# SparkFun_Main_Board_Double_v22.net
KiCad netlist of a schematic drawn in EAGLE
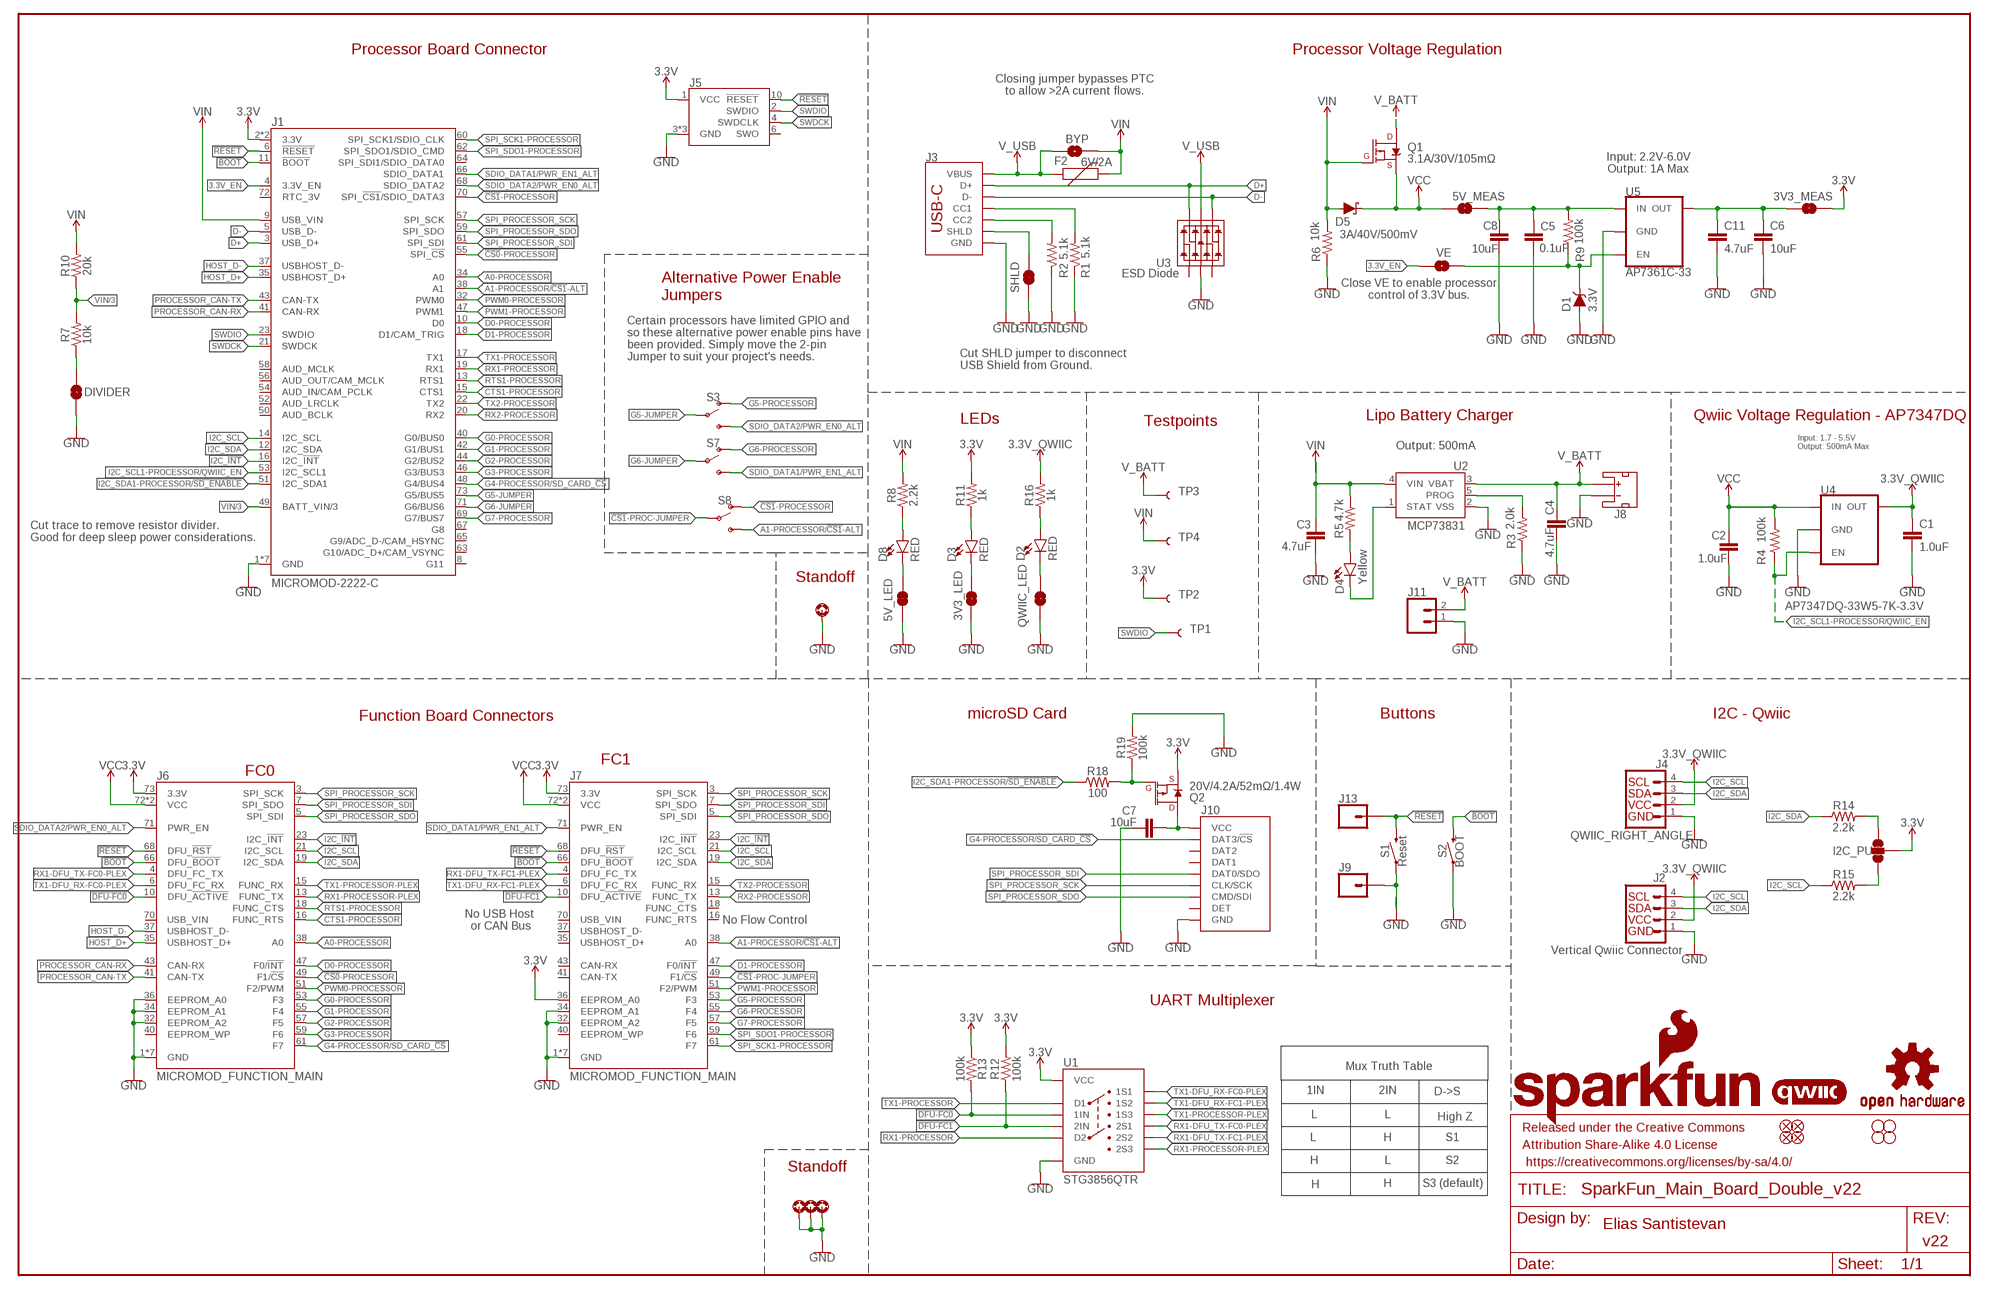
[diagram p0: schematic, sheet 1]

(export (version "E")
  (design (tool "Eeschema 10.0.6"))
  (components
    (comp (ref "3V3_LED")
      (value "JUMPER-SMT_2_NC_TRACE_SILK")
      (footprint "eagle-import:SMT-JUMPER_2_NC_TRACE_SILK")
      (libsource (lib "eagle-import") (part "JUMPER-SMT_2_NC_TRACE_SILK"))
    )
    (comp (ref "3V3_MEAS")
      (value "JUMPER-COMBO_2_NC_TRACE")
      (footprint "eagle-import:COMBO-JUMPER_2_NC_TRACE")
      (libsource (lib "eagle-import") (part "JUMPER-COMBO_2_NC_TRACE"))
    )
    (comp (ref "5V_LED")
      (value "JUMPER-SMT_2_NC_TRACE_SILK")
      (footprint "eagle-import:SMT-JUMPER_2_NC_TRACE_SILK")
      (libsource (lib "eagle-import") (part "JUMPER-SMT_2_NC_TRACE_SILK"))
    )
    (comp (ref "5V_MEAS")
      (value "JUMPER-COMBO_2_NC_TRACE")
      (footprint "eagle-import:COMBO-JUMPER_2_NC_TRACE")
      (libsource (lib "eagle-import") (part "JUMPER-COMBO_2_NC_TRACE"))
    )
    (comp (ref "BYP")
      (value "JUMPER-SMT_2_NO_SILK")
      (footprint "eagle-import:SMT-JUMPER_2_NO_SILK")
      (libsource (lib "eagle-import") (part "JUMPER-SMT_2_NO_SILK"))
    )
    (comp (ref "C1")
      (value "1.0uF")
      (footprint "eagle-import:0603")
      (libsource (lib "eagle-import") (part "1.0UF-0603-16V-10%"))
    )
    (comp (ref "C2")
      (value "1.0uF")
      (footprint "eagle-import:0603")
      (libsource (lib "eagle-import") (part "1.0UF-0603-16V-10%"))
    )
    (comp (ref "C3")
      (value "4.7uF")
      (footprint "eagle-import:0603")
      (libsource (lib "eagle-import") (part "4.7UF-0603-6.3V-(10%)"))
    )
    (comp (ref "C4")
      (value "4.7uF")
      (footprint "eagle-import:0603")
      (libsource (lib "eagle-import") (part "4.7UF-0603-35V-(20%)"))
    )
    (comp (ref "C5")
      (value "0.1uF")
      (footprint "eagle-import:0603")
      (libsource (lib "eagle-import") (part "0.1UF-0603-25V-(+80/-20%)"))
    )
    (comp (ref "C6")
      (value "10uF")
      (footprint "eagle-import:0805")
      (libsource (lib "eagle-import") (part "10UF-0805-10V-10%"))
    )
    (comp (ref "C7")
      (value "10uF")
      (footprint "eagle-import:0603")
      (libsource (lib "eagle-import") (part "10UF-0603-6.3V-20%"))
    )
    (comp (ref "C8")
      (value "10uF")
      (footprint "eagle-import:0805")
      (libsource (lib "eagle-import") (part "10UF-0805-10V-10%"))
    )
    (comp (ref "C11")
      (value "4.7uF")
      (footprint "eagle-import:0603")
      (libsource (lib "eagle-import") (part "4.7UF-0603-6.3V-(10%)"))
    )
    (comp (ref "D1")
      (value "3.3V")
      (footprint "eagle-import:SOD-323")
      (libsource (lib "eagle-import") (part "DIODE-ZENER-MM3Z3V3T1G"))
    )
    (comp (ref "D2")
      (value "RED")
      (footprint "eagle-import:LED-0603")
      (libsource (lib "eagle-import") (part "LED-RED0603"))
    )
    (comp (ref "D3")
      (value "RED")
      (footprint "eagle-import:LED-0603")
      (libsource (lib "eagle-import") (part "LED-RED0603"))
    )
    (comp (ref "D4")
      (value "Yellow")
      (footprint "eagle-import:LED-0603")
      (libsource (lib "eagle-import") (part "LED-YELLOW0603"))
    )
    (comp (ref "D5")
      (value "3A/40V/500mV")
      (footprint "eagle-import:SMA-DIODE")
      (libsource (lib "eagle-import") (part "DIODE-SCHOTTKY-B340A"))
    )
    (comp (ref "D8")
      (value "RED")
      (footprint "eagle-import:LED-0603")
      (libsource (lib "eagle-import") (part "LED-RED0603"))
    )
    (comp (ref "DIVIDER")
      (value "JUMPER-SMT_2_NC_TRACE_SILK")
      (footprint "eagle-import:SMT-JUMPER_2_NC_TRACE_SILK")
      (libsource (lib "eagle-import") (part "JUMPER-SMT_2_NC_TRACE_SILK"))
    )
    (comp (ref "F2")
      (value "6V/2A")
      (footprint "eagle-import:1210")
      (libsource (lib "eagle-import") (part "PPTC_6V2A"))
    )
    (comp (ref "FD1")
      (value "FIDUCIAL1X2")
      (footprint "eagle-import:FIDUCIAL-1X2")
      (libsource (lib "eagle-import") (part "FIDUCIAL1X2"))
    )
    (comp (ref "FD2")
      (value "FIDUCIAL1X2")
      (footprint "eagle-import:FIDUCIAL-1X2")
      (libsource (lib "eagle-import") (part "FIDUCIAL1X2"))
    )
    (comp (ref "FD3")
      (value "FIDUCIAL1X2")
      (footprint "eagle-import:FIDUCIAL-1X2")
      (libsource (lib "eagle-import") (part "FIDUCIAL1X2"))
    )
    (comp (ref "FD4")
      (value "FIDUCIAL1X2")
      (footprint "eagle-import:FIDUCIAL-1X2")
      (libsource (lib "eagle-import") (part "FIDUCIAL1X2"))
    )
    (comp (ref "FRAME1")
      (value "FRAME-LEDGER")
      (footprint "eagle-import:CREATIVE_COMMONS")
      (libsource (lib "eagle-import") (part "FRAME-LEDGER"))
    )
    (comp (ref "H2")
      (value "STAND-OFF-REFLOW-M2.5_2.5MM_TALL")
      (footprint "eagle-import:STAND-OFF-REFLOW-M2.5")
      (libsource (lib "eagle-import") (part "STAND-OFF-REFLOW-M2.5_2.5MM_TALL"))
    )
    (comp (ref "H3")
      (value "STAND-OFF-REFLOW-M2.5_2.5MM_TALL")
      (footprint "eagle-import:STAND-OFF-REFLOW-M2.5")
      (libsource (lib "eagle-import") (part "STAND-OFF-REFLOW-M2.5_2.5MM_TALL"))
    )
    (comp (ref "H4")
      (value "STAND-OFF-REFLOW-M2.5_2.5MM_TALL")
      (footprint "eagle-import:STAND-OFF-REFLOW-M2.5")
      (libsource (lib "eagle-import") (part "STAND-OFF-REFLOW-M2.5_2.5MM_TALL"))
    )
    (comp (ref "H8")
      (value "STAND-OFF-REFLOW-M2.5_2.5MM_TALL")
      (footprint "eagle-import:STAND-OFF-REFLOW-M2.5")
      (libsource (lib "eagle-import") (part "STAND-OFF-REFLOW-M2.5_2.5MM_TALL"))
    )
    (comp (ref "H14")
      (value "STAND-OFFTIGHT")
      (footprint "eagle-import:STAND-OFF-TIGHT")
      (libsource (lib "eagle-import") (part "STAND-OFFTIGHT"))
    )
    (comp (ref "H15")
      (value "STAND-OFFTIGHT")
      (footprint "eagle-import:STAND-OFF-TIGHT")
      (libsource (lib "eagle-import") (part "STAND-OFFTIGHT"))
    )
    (comp (ref "H16")
      (value "STAND-OFFTIGHT")
      (footprint "eagle-import:STAND-OFF-TIGHT")
      (libsource (lib "eagle-import") (part "STAND-OFFTIGHT"))
    )
    (comp (ref "H17")
      (value "STAND-OFFTIGHT")
      (footprint "eagle-import:STAND-OFF-TIGHT")
      (libsource (lib "eagle-import") (part "STAND-OFFTIGHT"))
    )
    (comp (ref "I2C_PU")
      (value "JUMPER-SMT_3_2-NC_TRACE_SILK")
      (footprint "eagle-import:SMT-JUMPER_3_2-NC_TRACE_SILK")
      (libsource (lib "eagle-import") (part "JUMPER-SMT_3_2-NC_TRACE_SILK"))
    )
    (comp (ref "J1")
      (value "MICROMOD-2222-C")
      (footprint "eagle-import:M.2-CONNECTOR-E")
      (libsource (lib "eagle-import") (part "MICROMOD-2222-C"))
    )
    (comp (ref "J2")
      (value "Vertical Qwiic Connector")
      (footprint "eagle-import:JST04_1MM_VERT")
      (libsource (lib "eagle-import") (part "QWIIC_CONNECTOR"))
    )
    (comp (ref "J3")
      (value "USB_C_2-LAYER_PADS")
      (footprint "eagle-import:USB-C-16P-2LAYER-PADS")
      (libsource (lib "eagle-import") (part "USB_C_2-LAYER_PADS"))
    )
    (comp (ref "J4")
      (value "QWIIC_RIGHT_ANGLE")
      (footprint "eagle-import:JST04_1MM_RA")
      (libsource (lib "eagle-import") (part "QWIIC_CONNECTORJS-1MM"))
    )
    (comp (ref "J5")
      (value "CORTEX_JTAG_DEBUG_MINIMUM_PTH")
      (footprint "eagle-import:2X5-PTH-1.27MM")
      (libsource (lib "eagle-import") (part "CORTEX_JTAG_DEBUG_MINIMUM_PTH"))
    )
    (comp (ref "J6")
      (value "MICROMOD_FUNCTION_MAIN")
      (footprint "eagle-import:M.2-CONNECTOR-E-FUNCTION-STANDARD")
      (libsource (lib "eagle-import") (part "MICROMOD_FUNCTION_MAIN"))
    )
    (comp (ref "J7")
      (value "MICROMOD_FUNCTION_MAIN")
      (footprint "eagle-import:M.2-CONNECTOR-E-FUNCTION-STANDARD")
      (libsource (lib "eagle-import") (part "MICROMOD_FUNCTION_MAIN"))
    )
    (comp (ref "J8")
      (value "JST_2MM_MALE")
      (footprint "eagle-import:JST-2-SMD")
      (libsource (lib "eagle-import") (part "JST_2MM_MALE"))
    )
    (comp (ref "J9")
      (value "CONN_01PTH_NO_SILK_YES_STOP")
      (footprint "eagle-import:1X01_NO_SILK")
      (libsource (lib "eagle-import") (part "CONN_01PTH_NO_SILK_YES_STOP"))
    )
    (comp (ref "J10")
      (value "MICRO-SD-PUSH-PUSH-EXT-PIN")
      (footprint "eagle-import:MICROSD-EXTERNALPIN")
      (libsource (lib "eagle-import") (part "MICRO-SD-PUSH-PUSH-EXT-PIN"))
    )
    (comp (ref "J11")
      (value "CONN_021X02_NO_SILK")
      (footprint "eagle-import:1X02_NO_SILK")
      (libsource (lib "eagle-import") (part "CONN_021X02_NO_SILK"))
    )
    (comp (ref "J13")
      (value "CONN_01PTH_NO_SILK_YES_STOP")
      (footprint "eagle-import:1X01_NO_SILK")
      (libsource (lib "eagle-import") (part "CONN_01PTH_NO_SILK_YES_STOP"))
    )
    (comp (ref "LOGO1")
      (value "QWIIC_LOGO_8MM")
      (footprint "eagle-import:QWIIC_8MM")
      (libsource (lib "eagle-import") (part "QWIIC_LOGO_8MM"))
    )
    (comp (ref "LOGO2")
      (value "SFE_LOGO_NAME_FLAME.3_INCH")
      (footprint "eagle-import:SFE_LOGO_NAME_FLAME_.3")
      (libsource (lib "eagle-import") (part "SFE_LOGO_NAME_FLAME.3_INCH"))
    )
    (comp (ref "LOGO3")
      (value "OSHW-LOGOL")
      (footprint "eagle-import:OSHW-LOGO-L")
      (libsource (lib "eagle-import") (part "OSHW-LOGOL"))
    )
    (comp (ref "Q1")
      (value "3.1A/30V/105mΩ")
      (footprint "eagle-import:SOT23-3")
      (libsource (lib "eagle-import") (part "MOSFET_PCH-DMG2307L"))
    )
    (comp (ref "Q2")
      (value "20V/4.2A/52mΩ/1.4W")
      (footprint "eagle-import:SOT23-3")
      (libsource (lib "eagle-import") (part "MOSFET_PCH-DMG2305UX-7"))
    )
    (comp (ref "QWIIC_LED")
      (value "JUMPER-SMT_2_NC_TRACE_SILK")
      (footprint "eagle-import:SMT-JUMPER_2_NC_TRACE_SILK")
      (libsource (lib "eagle-import") (part "JUMPER-SMT_2_NC_TRACE_SILK"))
    )
    (comp (ref "R1")
      (value "5.1k")
      (footprint "eagle-import:0603")
      (libsource (lib "eagle-import") (part "5.1KOHM5.1KOHM-0603-1/10W-1%"))
    )
    (comp (ref "R2")
      (value "5.1k")
      (footprint "eagle-import:0603")
      (libsource (lib "eagle-import") (part "5.1KOHM5.1KOHM-0603-1/10W-1%"))
    )
    (comp (ref "R3")
      (value "2.0k")
      (footprint "eagle-import:0603")
      (libsource (lib "eagle-import") (part "2.0KOHM-0603-1/10W-5%"))
    )
    (comp (ref "R4")
      (value "100k")
      (footprint "eagle-import:0603")
      (libsource (lib "eagle-import") (part "100KOHM-0603-1/10W-1%"))
    )
    (comp (ref "R5")
      (value "4.7k")
      (footprint "eagle-import:0603")
      (libsource (lib "eagle-import") (part "4.7KOHM-0603-1/10W-1%"))
    )
    (comp (ref "R6")
      (value "10k")
      (footprint "eagle-import:0603")
      (libsource (lib "eagle-import") (part "10KOHM-0603-1/10W-1%"))
    )
    (comp (ref "R7")
      (value "10k")
      (footprint "eagle-import:0603")
      (libsource (lib "eagle-import") (part "10KOHM-0603-1/10W-1%"))
    )
    (comp (ref "R8")
      (value "2.2k")
      (footprint "eagle-import:0603")
      (libsource (lib "eagle-import") (part "2.2KOHM-0603-1/10W-1%"))
    )
    (comp (ref "R9")
      (value "100k")
      (footprint "eagle-import:0603")
      (libsource (lib "eagle-import") (part "100KOHM-0603-1/10W-1%"))
    )
    (comp (ref "R10")
      (value "20k")
      (footprint "eagle-import:0603")
      (libsource (lib "eagle-import") (part "20KOHM-0603-1/10W-1%"))
    )
    (comp (ref "R11")
      (value "1k")
      (footprint "eagle-import:0603")
      (libsource (lib "eagle-import") (part "1KOHM-0603-1/10W-1%"))
    )
    (comp (ref "R12")
      (value "100k")
      (footprint "eagle-import:0603")
      (libsource (lib "eagle-import") (part "100KOHM-0603-1/10W-1%"))
    )
    (comp (ref "R13")
      (value "100k")
      (footprint "eagle-import:0603")
      (libsource (lib "eagle-import") (part "100KOHM-0603-1/10W-1%"))
    )
    (comp (ref "R14")
      (value "2.2k")
      (footprint "eagle-import:0603")
      (libsource (lib "eagle-import") (part "2.2KOHM-0603-1/10W-1%"))
    )
    (comp (ref "R15")
      (value "2.2k")
      (footprint "eagle-import:0603")
      (libsource (lib "eagle-import") (part "2.2KOHM-0603-1/10W-1%"))
    )
    (comp (ref "R16")
      (value "1k")
      (footprint "eagle-import:0603")
      (libsource (lib "eagle-import") (part "1KOHM-0603-1/10W-1%"))
    )
    (comp (ref "R18")
      (value "100")
      (footprint "eagle-import:0603")
      (libsource (lib "eagle-import") (part "100OHM-0603-1/10W-1%"))
    )
    (comp (ref "R19")
      (value "100k")
      (footprint "eagle-import:0603")
      (libsource (lib "eagle-import") (part "100KOHM-0603-1/10W-1%"))
    )
    (comp (ref "S1")
      (value "Reset")
      (footprint "eagle-import:TACTILE_SWITCH_SMD_5.2MM")
      (libsource (lib "eagle-import") (part "MOMENTARY-SWITCH-SPST-SMD-5.2-TALL-REDUNDANT"))
    )
    (comp (ref "S2")
      (value "BOOT")
      (footprint "eagle-import:TACTILE_SWITCH_SMD_5.2MM")
      (libsource (lib "eagle-import") (part "MOMENTARY-SWITCH-SPST-SMD-5.2-TALL-REDUNDANT"))
    )
    (comp (ref "S3")
      (value "SWITCH-SPDT-SMD-RIGHT-ANGLE")
      (footprint "eagle-import:SWITCH_SPST_SMD_A")
      (libsource (lib "eagle-import") (part "SWITCH-SPDT-SMD-RIGHT-ANGLE"))
    )
    (comp (ref "S7")
      (value "SWITCH-SPDT-SMD-RIGHT-ANGLE")
      (footprint "eagle-import:SWITCH_SPST_SMD_A")
      (libsource (lib "eagle-import") (part "SWITCH-SPDT-SMD-RIGHT-ANGLE"))
    )
    (comp (ref "S8")
      (value "SWITCH-SPDT-SMD-RIGHT-ANGLE")
      (footprint "eagle-import:SWITCH_SPST_SMD_A")
      (libsource (lib "eagle-import") (part "SWITCH-SPDT-SMD-RIGHT-ANGLE"))
    )
    (comp (ref "SHLD")
      (value "JUMPER-SMT_2_NC_TRACE_SILK")
      (footprint "eagle-import:SMT-JUMPER_2_NC_TRACE_SILK")
      (libsource (lib "eagle-import") (part "JUMPER-SMT_2_NC_TRACE_SILK"))
    )
    (comp (ref "TP1")
      (value "TEST-POINT3X5")
      (footprint "eagle-import:PAD.03X.05")
      (libsource (lib "eagle-import") (part "TEST-POINT3X5"))
    )
    (comp (ref "TP2")
      (value "TEST-POINT3X5")
      (footprint "eagle-import:PAD.03X.05")
      (libsource (lib "eagle-import") (part "TEST-POINT3X5"))
    )
    (comp (ref "TP3")
      (value "TEST-POINT3X5")
      (footprint "eagle-import:PAD.03X.05")
      (libsource (lib "eagle-import") (part "TEST-POINT3X5"))
    )
    (comp (ref "TP4")
      (value "TEST-POINT3X5")
      (footprint "eagle-import:PAD.03X.05")
      (libsource (lib "eagle-import") (part "TEST-POINT3X5"))
    )
    (comp (ref "U1")
      (value "STG3856QTR")
      (footprint "eagle-import:STG3856")
      (libsource (lib "eagle-import") (part "STG3856QTR"))
    )
    (comp (ref "U2")
      (value "MCP73831")
      (footprint "eagle-import:SOT23-5")
      (libsource (lib "eagle-import") (part "MCP73831"))
    )
    (comp (ref "U3")
      (value "ESD Diode")
      (footprint "eagle-import:SOT-23-6")
      (libsource (lib "eagle-import") (part "TVS_DIODE_ARRAYSMD"))
    )
    (comp (ref "U4")
      (value "AP7347DQ-33W5-7K-3.3V")
      (footprint "eagle-import:SOT25")
      (libsource (lib "eagle-import") (part "AP7347DQ-33W5-7K-3.3V"))
    )
    (comp (ref "U5")
      (value "AP7361C-33")
      (footprint "eagle-import:UDFN-8")
      (libsource (lib "eagle-import") (part "AP7361C-33FGEUDFN-8"))
    )
    (comp (ref "VE")
      (value "JUMPER-SMT_2_NO_SILK")
      (footprint "eagle-import:SMT-JUMPER_2_NO_SILK")
      (libsource (lib "eagle-import") (part "JUMPER-SMT_2_NO_SILK"))
    )
  )
  (nets
    (net (code "1") (name "/A1-PROCESSOR{slash}~{CS1}-ALT") (class "Default")
      (node (ref "J1") (pin "38") (pinfunction "A1_38") (pintype "bidirectional"))
      (node (ref "J7") (pin "38") (pinfunction "A0_38") (pintype "bidirectional"))
      (node (ref "S8") (pin "3") (pinfunction "S_3") (pintype "passive"))
    )
    (net (code "2") (name "/G4-PROCESSOR{slash}SD_CARD_~{CS}") (class "Default")
      (node (ref "J1") (pin "48") (pinfunction "G4/BUS4_48") (pintype "bidirectional"))
      (node (ref "J10") (pin "2") (pinfunction "DAT3/~{CS}_2") (pintype "bidirectional"))
      (node (ref "J6") (pin "61") (pinfunction "F7_61") (pintype "bidirectional"))
    )
    (net (code "3") (name "/I2C_SDA1-PROCESSOR{slash}~{SD_ENABLE}") (class "Default")
      (node (ref "J1") (pin "51") (pinfunction "I2C_SDA1_51") (pintype "bidirectional"))
      (node (ref "R18") (pin "1") (pinfunction "1_1") (pintype "passive"))
    )
    (net (code "4") (name "/I2C_~{INT}") (class "Default")
      (node (ref "J1") (pin "16") (pinfunction "I2C_~{INT}_16") (pintype "bidirectional"))
      (node (ref "J6") (pin "23") (pinfunction "I2C_~{INT}_23") (pintype "bidirectional"))
      (node (ref "J7") (pin "23") (pinfunction "I2C_~{INT}_23") (pintype "bidirectional"))
    )
    (net (code "5") (name "/~{BOOT}") (class "Default")
      (node (ref "J1") (pin "11") (pinfunction "~{BOOT}_11") (pintype "bidirectional"))
      (node (ref "J6") (pin "66") (pinfunction "DFU_~{BOOT}_66") (pintype "bidirectional"))
      (node (ref "J7") (pin "66") (pinfunction "DFU_~{BOOT}_66") (pintype "bidirectional"))
      (node (ref "S2") (pin "3") (pinfunction "2_3") (pintype "passive"))
      (node (ref "S2") (pin "4") (pinfunction "2_4") (pintype "passive"))
    )
    (net (code "6") (name "/~{CS0}-PROCESSOR") (class "Default")
      (node (ref "J1") (pin "55") (pinfunction "SPI_~{CS}_55") (pintype "bidirectional"))
      (node (ref "J6") (pin "49") (pinfunction "F1/~{CS}_49") (pintype "bidirectional"))
    )
    (net (code "7") (name "/~{CS1}-PROC-JUMPER") (class "Default")
      (node (ref "J7") (pin "49") (pinfunction "F1/~{CS}_49") (pintype "bidirectional"))
      (node (ref "S8") (pin "2") (pinfunction "P_2") (pintype "passive"))
    )
    (net (code "8") (name "/~{CS1}-PROCESSOR") (class "Default")
      (node (ref "J1") (pin "70") (pinfunction "SPI_~{CS1}/SDIO_DATA3_70") (pintype "bidirectional"))
      (node (ref "S8") (pin "1") (pinfunction "O_1") (pintype "passive"))
    )
    (net (code "9") (name "/~{DFU-FC0}") (class "Default")
      (node (ref "J6") (pin "10") (pinfunction "DFU_~{ACTIVE}_10") (pintype "bidirectional"))
      (node (ref "R13") (pin "2") (pinfunction "2_2") (pintype "passive"))
      (node (ref "U1") (pin "P12") (pinfunction "1IN_P12") (pintype "bidirectional"))
    )
    (net (code "10") (name "/~{DFU-FC1}") (class "Default")
      (node (ref "J7") (pin "10") (pinfunction "DFU_~{ACTIVE}_10") (pintype "bidirectional"))
      (node (ref "R12") (pin "1") (pinfunction "1_1") (pintype "passive"))
      (node (ref "U1") (pin "P10") (pinfunction "2IN_P10") (pintype "bidirectional"))
    )
    (net (code "11") (name "/~{RESET}") (class "Default")
      (node (ref "J1") (pin "6") (pinfunction "~{RESET}_6") (pintype "bidirectional"))
      (node (ref "J13") (pin "1") (pinfunction "1_1") (pintype "passive"))
      (node (ref "J5") (pin "10") (pinfunction "~{RESET}_10") (pintype "bidirectional"))
      (node (ref "J6") (pin "68") (pinfunction "DFU_~{RST}_68") (pintype "bidirectional"))
      (node (ref "J7") (pin "68") (pinfunction "DFU_~{RST}_68") (pintype "bidirectional"))
      (node (ref "S1") (pin "3") (pinfunction "2_3") (pintype "passive"))
      (node (ref "S1") (pin "4") (pinfunction "2_4") (pintype "passive"))
    )
    (net (code "12") (name "3.3V") (class "Default")
      (node (ref "3V3_MEAS") (pin "2") (pinfunction "2_2") (pintype "passive"))
      (node (ref "3V3_MEAS") (pin "4") (pinfunction "2_4") (pintype "passive"))
      (node (ref "I2C_PU") (pin "2") (pinfunction "2_2") (pintype "passive"))
      (node (ref "J1") (pin "2") (pinfunction "3.3V_2") (pintype "bidirectional"))
      (node (ref "J1") (pin "74") (pinfunction "3.3V_74") (pintype "bidirectional"))
      (node (ref "J5") (pin "1") (pinfunction "VCC_1") (pintype "bidirectional"))
      (node (ref "J6") (pin "73") (pinfunction "3.3V_73") (pintype "bidirectional"))
      (node (ref "J7") (pin "36") (pinfunction "EEPROM_A0_36") (pintype "bidirectional"))
      (node (ref "J7") (pin "73") (pinfunction "3.3V_73") (pintype "bidirectional"))
      (node (ref "Q2") (pin "2") (pinfunction "S_2") (pintype "bidirectional"))
      (node (ref "R11") (pin "2") (pinfunction "2_2") (pintype "passive"))
      (node (ref "R12") (pin "2") (pinfunction "2_2") (pintype "passive"))
      (node (ref "R13") (pin "1") (pinfunction "1_1") (pintype "passive"))
      (node (ref "TP2") (pin "1") (pinfunction "1_1") (pintype "bidirectional"))
      (node (ref "U1") (pin "P11") (pinfunction "VCC_P11") (pintype "power_in"))
    )
    (net (code "13") (name "3.3V_EN") (class "Default")
      (node (ref "J1") (pin "4") (pinfunction "3.3V_EN_4") (pintype "bidirectional"))
      (node (ref "VE") (pin "1") (pinfunction "1_1") (pintype "passive"))
    )
    (net (code "14") (name "3.3V_QWIIC") (class "Default")
      (node (ref "C1") (pin "1") (pinfunction "1_1") (pintype "passive"))
      (node (ref "J2") (pin "2") (pinfunction "2_2") (pintype "power_in"))
      (node (ref "J4") (pin "2") (pinfunction "2_2") (pintype "power_in"))
      (node (ref "R16") (pin "2") (pinfunction "2_2") (pintype "passive"))
      (node (ref "U4") (pin "5") (pinfunction "OUT_5") (pintype "passive"))
    )
    (net (code "15") (name "A0-PROCESSOR") (class "Default")
      (node (ref "J1") (pin "34") (pinfunction "A0_34") (pintype "bidirectional"))
      (node (ref "J6") (pin "38") (pinfunction "A0_38") (pintype "bidirectional"))
    )
    (net (code "16") (name "CTS1-PROCESSOR") (class "Default")
      (node (ref "J1") (pin "15") (pinfunction "CTS1_15") (pintype "bidirectional"))
      (node (ref "J6") (pin "16") (pinfunction "FUNC_RTS_16") (pintype "bidirectional"))
    )
    (net (code "17") (name "D+") (class "Default")
      (node (ref "J1") (pin "3") (pinfunction "USB_D+_3") (pintype "bidirectional"))
      (node (ref "J3") (pin "A6") (pinfunction "D+_A6") (pintype "bidirectional"))
      (node (ref "J3") (pin "B6") (pinfunction "D+_B6") (pintype "bidirectional"))
      (node (ref "U3") (pin "6") (pinfunction "IO4_6") (pintype "bidirectional"))
    )
    (net (code "18") (name "D-") (class "Default")
      (node (ref "J1") (pin "5") (pinfunction "USB_D-_5") (pintype "bidirectional"))
      (node (ref "J3") (pin "A7") (pinfunction "D-_A7") (pintype "bidirectional"))
      (node (ref "J3") (pin "B7") (pinfunction "D-_B7") (pintype "bidirectional"))
      (node (ref "U3") (pin "4") (pinfunction "IO3_4") (pintype "bidirectional"))
    )
    (net (code "19") (name "D0-PROCESSOR") (class "Default")
      (node (ref "J1") (pin "10") (pinfunction "D0_10") (pintype "bidirectional"))
      (node (ref "J6") (pin "47") (pinfunction "F0/~{INT}_47") (pintype "bidirectional"))
    )
    (net (code "20") (name "D1-PROCESSOR") (class "Default")
      (node (ref "J1") (pin "18") (pinfunction "D1/CAM_TRIG_18") (pintype "bidirectional"))
      (node (ref "J7") (pin "47") (pinfunction "F0/~{INT}_47") (pintype "bidirectional"))
    )
    (net (code "21") (name "G0-PROCESSOR") (class "Default")
      (node (ref "J1") (pin "40") (pinfunction "G0/BUS0_40") (pintype "bidirectional"))
      (node (ref "J6") (pin "53") (pinfunction "F3_53") (pintype "bidirectional"))
    )
    (net (code "22") (name "G1-PROCESSOR") (class "Default")
      (node (ref "J1") (pin "42") (pinfunction "G1/BUS1_42") (pintype "bidirectional"))
      (node (ref "J6") (pin "55") (pinfunction "F4_55") (pintype "bidirectional"))
    )
    (net (code "23") (name "G2-PROCESSOR") (class "Default")
      (node (ref "J1") (pin "44") (pinfunction "G2/BUS2_44") (pintype "bidirectional"))
      (node (ref "J6") (pin "57") (pinfunction "F5_57") (pintype "bidirectional"))
    )
    (net (code "24") (name "G3-PROCESSOR") (class "Default")
      (node (ref "J1") (pin "46") (pinfunction "G3/BUS3_46") (pintype "bidirectional"))
      (node (ref "J6") (pin "59") (pinfunction "F6_59") (pintype "bidirectional"))
    )
    (net (code "25") (name "G5-JUMPER") (class "Default")
      (node (ref "J1") (pin "73") (pinfunction "G5/BUS5_73") (pintype "bidirectional"))
      (node (ref "S3") (pin "2") (pinfunction "P_2") (pintype "passive"))
    )
    (net (code "26") (name "G5-PROCESSOR") (class "Default")
      (node (ref "J7") (pin "53") (pinfunction "F3_53") (pintype "bidirectional"))
      (node (ref "S3") (pin "1") (pinfunction "O_1") (pintype "passive"))
    )
    (net (code "27") (name "G6-JUMPER") (class "Default")
      (node (ref "J1") (pin "71") (pinfunction "G6/BUS6_71") (pintype "bidirectional"))
      (node (ref "S7") (pin "2") (pinfunction "P_2") (pintype "passive"))
    )
    (net (code "28") (name "G6-PROCESSOR") (class "Default")
      (node (ref "J7") (pin "55") (pinfunction "F4_55") (pintype "bidirectional"))
      (node (ref "S7") (pin "1") (pinfunction "O_1") (pintype "passive"))
    )
    (net (code "29") (name "G7-PROCESSOR") (class "Default")
      (node (ref "J1") (pin "69") (pinfunction "G7/BUS7_69") (pintype "bidirectional"))
      (node (ref "J7") (pin "57") (pinfunction "F5_57") (pintype "bidirectional"))
    )
    (net (code "30") (name "GND") (class "Default")
      (node (ref "3V3_LED") (pin "1") (pinfunction "1_1") (pintype "passive"))
      (node (ref "5V_LED") (pin "1") (pinfunction "1_1") (pintype "passive"))
      (node (ref "C1") (pin "2") (pinfunction "2_2") (pintype "passive"))
      (node (ref "C11") (pin "2") (pinfunction "2_2") (pintype "passive"))
      (node (ref "C2") (pin "2") (pinfunction "2_2") (pintype "passive"))
      (node (ref "C3") (pin "2") (pinfunction "2_2") (pintype "passive"))
      (node (ref "C4") (pin "2") (pinfunction "2_2") (pintype "passive"))
      (node (ref "C5") (pin "2") (pinfunction "2_2") (pintype "passive"))
      (node (ref "C6") (pin "2") (pinfunction "2_2") (pintype "passive"))
      (node (ref "C7") (pin "1") (pinfunction "1_1") (pintype "passive"))
      (node (ref "C8") (pin "2") (pinfunction "2_2") (pintype "passive"))
      (node (ref "D1") (pin "A") (pinfunction "A_A") (pintype "passive"))
      (node (ref "DIVIDER") (pin "1") (pinfunction "1_1") (pintype "passive"))
      (node (ref "H2") (pin "1") (pinfunction "1_1") (pintype "bidirectional"))
      (node (ref "H3") (pin "1") (pinfunction "1_1") (pintype "bidirectional"))
      (node (ref "H4") (pin "1") (pinfunction "1_1") (pintype "bidirectional"))
      (node (ref "H8") (pin "1") (pinfunction "1_1") (pintype "bidirectional"))
      (node (ref "J1") (pin "1") (pinfunction "GND_1") (pintype "bidirectional"))
      (node (ref "J1") (pin "33") (pinfunction "GND_33") (pintype "bidirectional"))
      (node (ref "J1") (pin "36") (pinfunction "GND_36") (pintype "bidirectional"))
      (node (ref "J1") (pin "39") (pinfunction "GND_39") (pintype "bidirectional"))
      (node (ref "J1") (pin "45") (pinfunction "GND_45") (pintype "bidirectional"))
      (node (ref "J1") (pin "7") (pinfunction "GND_7") (pintype "bidirectional"))
      (node (ref "J1") (pin "75") (pinfunction "GND_75") (pintype "bidirectional"))
      (node (ref "J10") (pin "10") (pinfunction "GND_10") (pintype "bidirectional"))
      (node (ref "J10") (pin "11") (pinfunction "GND_11") (pintype "bidirectional"))
      (node (ref "J10") (pin "12") (pinfunction "GND_12") (pintype "bidirectional"))
      (node (ref "J10") (pin "13") (pinfunction "GND_13") (pintype "bidirectional"))
      (node (ref "J10") (pin "6") (pinfunction "GND_6") (pintype "bidirectional"))
      (node (ref "J11") (pin "1") (pinfunction "1_1") (pintype "passive"))
      (node (ref "J2") (pin "1") (pinfunction "1_1") (pintype "power_in"))
      (node (ref "J3") (pin "GND") (pinfunction "GND_GND") (pintype "bidirectional"))
      (node (ref "J3") (pin "GND2") (pinfunction "GND_GND2") (pintype "bidirectional"))
      (node (ref "J4") (pin "1") (pinfunction "1_1") (pintype "power_in"))
      (node (ref "J5") (pin "3") (pinfunction "GND_3") (pintype "bidirectional"))
      (node (ref "J5") (pin "5") (pinfunction "GND_5") (pintype "bidirectional"))
      (node (ref "J5") (pin "9") (pinfunction "GND_9") (pintype "bidirectional"))
      (node (ref "J6") (pin "1") (pinfunction "GND_1") (pintype "bidirectional"))
      (node (ref "J6") (pin "2") (pinfunction "GND_2") (pintype "bidirectional"))
      (node (ref "J6") (pin "32") (pinfunction "EEPROM_A2_32") (pintype "bidirectional"))
      (node (ref "J6") (pin "33") (pinfunction "GND_33") (pintype "bidirectional"))
      (node (ref "J6") (pin "34") (pinfunction "EEPROM_A1_34") (pintype "bidirectional"))
      (node (ref "J6") (pin "36") (pinfunction "EEPROM_A0_36") (pintype "bidirectional"))
      (node (ref "J6") (pin "39") (pinfunction "GND_39") (pintype "bidirectional"))
      (node (ref "J6") (pin "45") (pinfunction "GND_45") (pintype "bidirectional"))
      (node (ref "J6") (pin "75") (pinfunction "GND_75") (pintype "bidirectional"))
      (node (ref "J6") (pin "8") (pinfunction "GND_8") (pintype "bidirectional"))
      (node (ref "J7") (pin "1") (pinfunction "GND_1") (pintype "bidirectional"))
      (node (ref "J7") (pin "2") (pinfunction "GND_2") (pintype "bidirectional"))
      (node (ref "J7") (pin "32") (pinfunction "EEPROM_A2_32") (pintype "bidirectional"))
      (node (ref "J7") (pin "33") (pinfunction "GND_33") (pintype "bidirectional"))
      (node (ref "J7") (pin "34") (pinfunction "EEPROM_A1_34") (pintype "bidirectional"))
      (node (ref "J7") (pin "39") (pinfunction "GND_39") (pintype "bidirectional"))
      (node (ref "J7") (pin "45") (pinfunction "GND_45") (pintype "bidirectional"))
      (node (ref "J7") (pin "75") (pinfunction "GND_75") (pintype "bidirectional"))
      (node (ref "J7") (pin "8") (pinfunction "GND_8") (pintype "bidirectional"))
      (node (ref "J8") (pin "1") (pinfunction "-_1") (pintype "bidirectional"))
      (node (ref "J9") (pin "1") (pinfunction "1_1") (pintype "passive"))
      (node (ref "QWIIC_LED") (pin "1") (pinfunction "1_1") (pintype "passive"))
      (node (ref "R1") (pin "1") (pinfunction "1_1") (pintype "passive"))
      (node (ref "R19") (pin "2") (pinfunction "2_2") (pintype "passive"))
      (node (ref "R2") (pin "1") (pinfunction "1_1") (pintype "passive"))
      (node (ref "R3") (pin "1") (pinfunction "1_1") (pintype "passive"))
      (node (ref "R6") (pin "1") (pinfunction "1_1") (pintype "passive"))
      (node (ref "S1") (pin "1") (pinfunction "1_1") (pintype "passive"))
      (node (ref "S1") (pin "2") (pinfunction "1_2") (pintype "passive"))
      (node (ref "S2") (pin "1") (pinfunction "1_1") (pintype "passive"))
      (node (ref "S2") (pin "2") (pinfunction "1_2") (pintype "passive"))
      (node (ref "SHLD") (pin "1") (pinfunction "1_1") (pintype "passive"))
      (node (ref "U1") (pin "P5") (pinfunction "GND_P5") (pintype "power_in"))
      (node (ref "U2") (pin "2") (pinfunction "VSS_2") (pintype "power_in"))
      (node (ref "U3") (pin "2") (pinfunction "VSS_2") (pintype "bidirectional"))
      (node (ref "U4") (pin "2") (pinfunction "GND_2") (pintype "input"))
      (node (ref "U5") (pin "4") (pinfunction "GND_4") (pintype "input"))
      (node (ref "U5") (pin "EP") (pinfunction "GND_EP") (pintype "input"))
    )
    (net (code "31") (name "HOST_D+") (class "Default")
      (node (ref "J1") (pin "35") (pinfunction "USBHOST_D+_35") (pintype "bidirectional"))
      (node (ref "J6") (pin "35") (pinfunction "USBHOST_D+_35") (pintype "bidirectional"))
    )
    (net (code "32") (name "HOST_D-") (class "Default")
      (node (ref "J1") (pin "37") (pinfunction "USBHOST_D-_37") (pintype "bidirectional"))
      (node (ref "J6") (pin "37") (pinfunction "USBHOST_D-_37") (pintype "bidirectional"))
    )
    (net (code "33") (name "I2C_SCL") (class "Default")
      (node (ref "J1") (pin "14") (pinfunction "I2C_SCL_14") (pintype "bidirectional"))
      (node (ref "J2") (pin "4") (pinfunction "4_4") (pintype "passive"))
      (node (ref "J4") (pin "4") (pinfunction "4_4") (pintype "passive"))
      (node (ref "J6") (pin "21") (pinfunction "I2C_SCL_21") (pintype "bidirectional"))
      (node (ref "J7") (pin "21") (pinfunction "I2C_SCL_21") (pintype "bidirectional"))
      (node (ref "R15") (pin "1") (pinfunction "1_1") (pintype "passive"))
    )
    (net (code "34") (name "I2C_SCL1-PROCESSOR{slash}QWIIC_EN") (class "Default")
      (node (ref "J1") (pin "53") (pinfunction "I2C_SCL1_53") (pintype "bidirectional"))
      (node (ref "R4") (pin "1") (pinfunction "1_1") (pintype "passive"))
      (node (ref "U4") (pin "3") (pinfunction "EN_3") (pintype "input"))
    )
    (net (code "35") (name "I2C_SDA") (class "Default")
      (node (ref "J1") (pin "12") (pinfunction "I2C_SDA_12") (pintype "bidirectional"))
      (node (ref "J2") (pin "3") (pinfunction "3_3") (pintype "passive"))
      (node (ref "J4") (pin "3") (pinfunction "3_3") (pintype "passive"))
      (node (ref "J6") (pin "19") (pinfunction "I2C_SDA_19") (pintype "bidirectional"))
      (node (ref "J7") (pin "19") (pinfunction "I2C_SDA_19") (pintype "bidirectional"))
      (node (ref "R14") (pin "1") (pinfunction "1_1") (pintype "passive"))
    )
    (net (code "36") (name "Net-(3V3_LED-Pad2)") (class "Default")
      (node (ref "3V3_LED") (pin "2") (pinfunction "2_2") (pintype "passive"))
      (node (ref "D3") (pin "C") (pinfunction "C_C") (pintype "passive"))
    )
    (net (code "37") (name "Net-(5V_LED-Pad2)") (class "Default")
      (node (ref "5V_LED") (pin "2") (pinfunction "2_2") (pintype "passive"))
      (node (ref "D8") (pin "C") (pinfunction "C_C") (pintype "passive"))
    )
    (net (code "38") (name "Net-(D2-PadA)") (class "Default")
      (node (ref "D2") (pin "A") (pinfunction "A_A") (pintype "passive"))
      (node (ref "R16") (pin "1") (pinfunction "1_1") (pintype "passive"))
    )
    (net (code "39") (name "Net-(D2-PadC)") (class "Default")
      (node (ref "D2") (pin "C") (pinfunction "C_C") (pintype "passive"))
      (node (ref "QWIIC_LED") (pin "2") (pinfunction "2_2") (pintype "passive"))
    )
    (net (code "40") (name "Net-(D3-PadA)") (class "Default")
      (node (ref "D3") (pin "A") (pinfunction "A_A") (pintype "passive"))
      (node (ref "R11") (pin "1") (pinfunction "1_1") (pintype "passive"))
    )
    (net (code "41") (name "Net-(D4-PadA)") (class "Default")
      (node (ref "D4") (pin "A") (pinfunction "A_A") (pintype "passive"))
      (node (ref "R5") (pin "2") (pinfunction "2_2") (pintype "passive"))
    )
    (net (code "42") (name "Net-(D8-PadA)") (class "Default")
      (node (ref "D8") (pin "A") (pinfunction "A_A") (pintype "passive"))
      (node (ref "R8") (pin "1") (pinfunction "1_1") (pintype "passive"))
    )
    (net (code "43") (name "Net-(DIVIDER-Pad2)") (class "Default")
      (node (ref "DIVIDER") (pin "2") (pinfunction "2_2") (pintype "passive"))
      (node (ref "R7") (pin "1") (pinfunction "1_1") (pintype "passive"))
    )
    (net (code "44") (name "Net-(I2C_PU-Pad1)") (class "Default")
      (node (ref "I2C_PU") (pin "1") (pinfunction "1_1") (pintype "passive"))
      (node (ref "R15") (pin "2") (pinfunction "2_2") (pintype "passive"))
    )
    (net (code "45") (name "Net-(I2C_PU-Pad3)") (class "Default")
      (node (ref "I2C_PU") (pin "3") (pinfunction "3_3") (pintype "passive"))
      (node (ref "R14") (pin "2") (pinfunction "2_2") (pintype "passive"))
    )
    (net (code "46") (name "Net-(J3-CC1)") (class "Default")
      (node (ref "J3") (pin "A5") (pinfunction "CC1_A5") (pintype "bidirectional"))
      (node (ref "R1") (pin "2") (pinfunction "2_2") (pintype "passive"))
    )
    (net (code "47") (name "Net-(J3-CC2)") (class "Default")
      (node (ref "J3") (pin "B5") (pinfunction "CC2_B5") (pintype "bidirectional"))
      (node (ref "R2") (pin "2") (pinfunction "2_2") (pintype "passive"))
    )
    (net (code "48") (name "Net-(J3-SHLD-PadSHLD1)") (class "Default")
      (node (ref "J3") (pin "SHLD1") (pinfunction "SHLD_SHLD1") (pintype "bidirectional"))
      (node (ref "J3") (pin "SHLD2") (pinfunction "SHLD_SHLD2") (pintype "bidirectional"))
      (node (ref "J3") (pin "SHLD3") (pinfunction "SHLD_SHLD3") (pintype "bidirectional"))
      (node (ref "J3") (pin "SHLD4") (pinfunction "SHLD_SHLD4") (pintype "bidirectional"))
      (node (ref "SHLD") (pin "2") (pinfunction "2_2") (pintype "passive"))
    )
    (net (code "49") (name "Net-(J10-VCC)") (class "Default")
      (node (ref "C7") (pin "2") (pinfunction "2_2") (pintype "passive"))
      (node (ref "J10") (pin "4") (pinfunction "VCC_4") (pintype "bidirectional"))
      (node (ref "Q2") (pin "3") (pinfunction "D_3") (pintype "bidirectional"))
    )
    (net (code "50") (name "Net-(Q2-G)") (class "Default")
      (node (ref "Q2") (pin "1") (pinfunction "G_1") (pintype "bidirectional"))
      (node (ref "R18") (pin "2") (pinfunction "2_2") (pintype "passive"))
      (node (ref "R19") (pin "1") (pinfunction "1_1") (pintype "passive"))
    )
    (net (code "51") (name "Net-(U2-PROG)") (class "Default")
      (node (ref "R3") (pin "2") (pinfunction "2_2") (pintype "passive"))
      (node (ref "U2") (pin "5") (pinfunction "PROG_5") (pintype "input"))
    )
    (net (code "52") (name "Net-(U2-STAT)") (class "Default")
      (node (ref "D4") (pin "C") (pinfunction "C_C") (pintype "passive"))
      (node (ref "U2") (pin "1") (pinfunction "STAT_1") (pintype "output"))
    )
    (net (code "53") (name "Net-(U5-EN)") (class "Default")
      (node (ref "D1") (pin "C") (pinfunction "C_C") (pintype "passive"))
      (node (ref "R9") (pin "1") (pinfunction "1_1") (pintype "passive"))
      (node (ref "U5") (pin "5") (pinfunction "EN_5") (pintype "bidirectional"))
      (node (ref "VE") (pin "2") (pinfunction "2_2") (pintype "passive"))
    )
    (net (code "54") (name "Net-(U5-IN)") (class "Default")
      (node (ref "5V_MEAS") (pin "2") (pinfunction "2_2") (pintype "passive"))
      (node (ref "5V_MEAS") (pin "4") (pinfunction "2_4") (pintype "passive"))
      (node (ref "C5") (pin "1") (pinfunction "1_1") (pintype "passive"))
      (node (ref "C8") (pin "1") (pinfunction "1_1") (pintype "passive"))
      (node (ref "R9") (pin "2") (pinfunction "2_2") (pintype "passive"))
      (node (ref "U5") (pin "8") (pinfunction "IN_8") (pintype "input"))
    )
    (net (code "55") (name "Net-(U5-OUT)") (class "Default")
      (node (ref "3V3_MEAS") (pin "1") (pinfunction "1_1") (pintype "passive"))
      (node (ref "3V3_MEAS") (pin "3") (pinfunction "1_3") (pintype "passive"))
      (node (ref "C11") (pin "1") (pinfunction "1_1") (pintype "passive"))
      (node (ref "C6") (pin "1") (pinfunction "1_1") (pintype "passive"))
      (node (ref "U5") (pin "1") (pinfunction "OUT_1") (pintype "output"))
    )
    (net (code "56") (name "PROCESSOR_CAN-RX") (class "Default")
      (node (ref "J1") (pin "41") (pinfunction "CAN-RX_41") (pintype "bidirectional"))
      (node (ref "J6") (pin "43") (pinfunction "CAN-RX_43") (pintype "bidirectional"))
    )
    (net (code "57") (name "PROCESSOR_CAN-TX") (class "Default")
      (node (ref "J1") (pin "43") (pinfunction "CAN-TX_43") (pintype "bidirectional"))
      (node (ref "J6") (pin "41") (pinfunction "CAN-TX_41") (pintype "bidirectional"))
    )
    (net (code "58") (name "PWM0-PROCESSOR") (class "Default")
      (node (ref "J1") (pin "32") (pinfunction "PWM0_32") (pintype "bidirectional"))
      (node (ref "J6") (pin "51") (pinfunction "F2/PWM_51") (pintype "bidirectional"))
    )
    (net (code "59") (name "PWM1-PROCESSOR") (class "Default")
      (node (ref "J1") (pin "47") (pinfunction "PWM1_47") (pintype "bidirectional"))
      (node (ref "J7") (pin "51") (pinfunction "F2/PWM_51") (pintype "bidirectional"))
    )
    (net (code "60") (name "RTS1-PROCESSOR") (class "Default")
      (node (ref "J1") (pin "13") (pinfunction "RTS1_13") (pintype "bidirectional"))
      (node (ref "J6") (pin "18") (pinfunction "FUNC_CTS_18") (pintype "bidirectional"))
    )
    (net (code "61") (name "RX1-DFU_TX-FC0-PLEX") (class "Default")
      (node (ref "J6") (pin "4") (pinfunction "DFU_FC_TX_4") (pintype "bidirectional"))
      (node (ref "U1") (pin "P9") (pinfunction "2S1_P9") (pintype "bidirectional"))
    )
    (net (code "62") (name "RX1-DFU_TX-FC1-PLEX") (class "Default")
      (node (ref "J7") (pin "4") (pinfunction "DFU_FC_TX_4") (pintype "bidirectional"))
      (node (ref "U1") (pin "P8") (pinfunction "2S2_P8") (pintype "bidirectional"))
    )
    (net (code "63") (name "RX1-PROCESSOR") (class "Default")
      (node (ref "J1") (pin "19") (pinfunction "RX1_19") (pintype "bidirectional"))
      (node (ref "U1") (pin "P6") (pinfunction "D2_P6") (pintype "bidirectional"))
    )
    (net (code "64") (name "RX1-PROCESSOR-PLEX") (class "Default")
      (node (ref "J6") (pin "13") (pinfunction "FUNC_TX_13") (pintype "bidirectional"))
      (node (ref "U1") (pin "P7") (pinfunction "2S3_P7") (pintype "bidirectional"))
    )
    (net (code "65") (name "RX2-PROCESSOR") (class "Default")
      (node (ref "J1") (pin "20") (pinfunction "RX2_20") (pintype "bidirectional"))
      (node (ref "J7") (pin "13") (pinfunction "FUNC_TX_13") (pintype "bidirectional"))
    )
    (net (code "66") (name "SDIO_DATA1{slash}PWR_EN1_ALT") (class "Default")
      (node (ref "J1") (pin "66") (pinfunction "SDIO_DATA1_66") (pintype "bidirectional"))
      (node (ref "J7") (pin "71") (pinfunction "PWR_EN_71") (pintype "bidirectional"))
      (node (ref "S7") (pin "3") (pinfunction "S_3") (pintype "passive"))
    )
    (net (code "67") (name "SDIO_DATA2{slash}PWR_EN0_ALT") (class "Default")
      (node (ref "J1") (pin "68") (pinfunction "SDIO_DATA2_68") (pintype "bidirectional"))
      (node (ref "J6") (pin "71") (pinfunction "PWR_EN_71") (pintype "bidirectional"))
      (node (ref "S3") (pin "3") (pinfunction "S_3") (pintype "passive"))
    )
    (net (code "68") (name "SPI_PROCESSOR_SCK") (class "Default")
      (node (ref "J1") (pin "57") (pinfunction "SPI_SCK_57") (pintype "bidirectional"))
      (node (ref "J10") (pin "5") (pinfunction "CLK/SCK_5") (pintype "bidirectional"))
      (node (ref "J6") (pin "3") (pinfunction "SPI_SCK_3") (pintype "bidirectional"))
      (node (ref "J7") (pin "3") (pinfunction "SPI_SCK_3") (pintype "bidirectional"))
    )
    (net (code "69") (name "SPI_PROCESSOR_SDI") (class "Default")
      (node (ref "J1") (pin "61") (pinfunction "SPI_SDI_61") (pintype "bidirectional"))
      (node (ref "J10") (pin "7") (pinfunction "DAT0/SDO_7") (pintype "bidirectional"))
      (node (ref "J6") (pin "7") (pinfunction "SPI_SDO_7") (pintype "bidirectional"))
      (node (ref "J7") (pin "7") (pinfunction "SPI_SDO_7") (pintype "bidirectional"))
    )
    (net (code "70") (name "SPI_PROCESSOR_SDO") (class "Default")
      (node (ref "J1") (pin "59") (pinfunction "SPI_SDO_59") (pintype "bidirectional"))
      (node (ref "J10") (pin "3") (pinfunction "CMD/SDI_3") (pintype "bidirectional"))
      (node (ref "J6") (pin "5") (pinfunction "SPI_SDI_5") (pintype "bidirectional"))
      (node (ref "J7") (pin "5") (pinfunction "SPI_SDI_5") (pintype "bidirectional"))
    )
    (net (code "71") (name "SPI_SCK1-PROCESSOR") (class "Default")
      (node (ref "J1") (pin "60") (pinfunction "SPI_SCK1/SDIO_CLK_60") (pintype "bidirectional"))
      (node (ref "J7") (pin "61") (pinfunction "F7_61") (pintype "bidirectional"))
    )
    (net (code "72") (name "SPI_SDO1-PROCESSOR") (class "Default")
      (node (ref "J1") (pin "62") (pinfunction "SPI_SDO1/SDIO_CMD_62") (pintype "bidirectional"))
      (node (ref "J7") (pin "59") (pinfunction "F6_59") (pintype "bidirectional"))
    )
    (net (code "73") (name "SWDCK") (class "Default")
      (node (ref "J1") (pin "21") (pinfunction "SWDCK_21") (pintype "bidirectional"))
      (node (ref "J5") (pin "4") (pinfunction "SWDCLK_4") (pintype "bidirectional"))
    )
    (net (code "74") (name "SWDIO") (class "Default")
      (node (ref "J1") (pin "23") (pinfunction "SWDIO_23") (pintype "bidirectional"))
      (node (ref "J5") (pin "2") (pinfunction "SWDIO_2") (pintype "bidirectional"))
      (node (ref "TP1") (pin "1") (pinfunction "1_1") (pintype "bidirectional"))
    )
    (net (code "75") (name "TX1-DFU_RX-FC0-PLEX") (class "Default")
      (node (ref "J6") (pin "6") (pinfunction "DFU_FC_RX_6") (pintype "bidirectional"))
      (node (ref "U1") (pin "P1") (pinfunction "1S1_P1") (pintype "bidirectional"))
    )
    (net (code "76") (name "TX1-DFU_RX-FC1-PLEX") (class "Default")
      (node (ref "J7") (pin "6") (pinfunction "DFU_FC_RX_6") (pintype "bidirectional"))
      (node (ref "U1") (pin "P2") (pinfunction "1S2_P2") (pintype "bidirectional"))
    )
    (net (code "77") (name "TX1-PROCESSOR") (class "Default")
      (node (ref "J1") (pin "17") (pinfunction "TX1_17") (pintype "bidirectional"))
      (node (ref "U1") (pin "P4") (pinfunction "D1_P4") (pintype "bidirectional"))
    )
    (net (code "78") (name "TX1-PROCESSOR-PLEX") (class "Default")
      (node (ref "J6") (pin "15") (pinfunction "FUNC_RX_15") (pintype "bidirectional"))
      (node (ref "U1") (pin "P3") (pinfunction "1S3_P3") (pintype "bidirectional"))
    )
    (net (code "79") (name "TX2-PROCESSOR") (class "Default")
      (node (ref "J1") (pin "22") (pinfunction "TX2_22") (pintype "bidirectional"))
      (node (ref "J7") (pin "15") (pinfunction "FUNC_RX_15") (pintype "bidirectional"))
    )
    (net (code "80") (name "VCC") (class "Default")
      (node (ref "5V_MEAS") (pin "1") (pinfunction "1_1") (pintype "passive"))
      (node (ref "5V_MEAS") (pin "3") (pinfunction "1_3") (pintype "passive"))
      (node (ref "C2") (pin "1") (pinfunction "1_1") (pintype "passive"))
      (node (ref "D5") (pin "C") (pinfunction "C_C") (pintype "passive"))
      (node (ref "J6") (pin "72") (pinfunction "VCC_72") (pintype "bidirectional"))
      (node (ref "J6") (pin "74") (pinfunction "VCC_74") (pintype "bidirectional"))
      (node (ref "J7") (pin "72") (pinfunction "VCC_72") (pintype "bidirectional"))
      (node (ref "J7") (pin "74") (pinfunction "VCC_74") (pintype "bidirectional"))
      (node (ref "Q1") (pin "2") (pinfunction "S_2") (pintype "bidirectional"))
      (node (ref "R4") (pin "2") (pinfunction "2_2") (pintype "passive"))
      (node (ref "U4") (pin "1") (pinfunction "IN_1") (pintype "input"))
    )
    (net (code "81") (name "VIN") (class "Default")
      (node (ref "BYP") (pin "2") (pinfunction "2_2") (pintype "passive"))
      (node (ref "C3") (pin "1") (pinfunction "1_1") (pintype "passive"))
      (node (ref "D5") (pin "A") (pinfunction "A_A") (pintype "passive"))
      (node (ref "F2") (pin "2") (pinfunction "2_2") (pintype "bidirectional"))
      (node (ref "J1") (pin "9") (pinfunction "USB_VIN_9") (pintype "bidirectional"))
      (node (ref "Q1") (pin "1") (pinfunction "G_1") (pintype "bidirectional"))
      (node (ref "R10") (pin "2") (pinfunction "2_2") (pintype "passive"))
      (node (ref "R5") (pin "1") (pinfunction "1_1") (pintype "passive"))
      (node (ref "R6") (pin "2") (pinfunction "2_2") (pintype "passive"))
      (node (ref "R8") (pin "2") (pinfunction "2_2") (pintype "passive"))
      (node (ref "TP4") (pin "1") (pinfunction "1_1") (pintype "bidirectional"))
      (node (ref "U2") (pin "4") (pinfunction "VIN_4") (pintype "power_in"))
    )
    (net (code "82") (name "VIN{slash}3") (class "Default")
      (node (ref "J1") (pin "49") (pinfunction "BATT_VIN/3_49") (pintype "bidirectional"))
      (node (ref "R10") (pin "1") (pinfunction "1_1") (pintype "passive"))
      (node (ref "R7") (pin "2") (pinfunction "2_2") (pintype "passive"))
    )
    (net (code "83") (name "V_BATT") (class "Default")
      (node (ref "C4") (pin "1") (pinfunction "1_1") (pintype "passive"))
      (node (ref "J11") (pin "2") (pinfunction "2_2") (pintype "passive"))
      (node (ref "J8") (pin "2") (pinfunction "+_2") (pintype "bidirectional"))
      (node (ref "Q1") (pin "3") (pinfunction "D_3") (pintype "bidirectional"))
      (node (ref "TP3") (pin "1") (pinfunction "1_1") (pintype "bidirectional"))
      (node (ref "U2") (pin "3") (pinfunction "VBAT_3") (pintype "power_in"))
    )
    (net (code "84") (name "V_USB") (class "Default")
      (node (ref "BYP") (pin "1") (pinfunction "1_1") (pintype "passive"))
      (node (ref "F2") (pin "1") (pinfunction "1_1") (pintype "bidirectional"))
      (node (ref "J3") (pin "VBUS1") (pinfunction "VBUS_VBUS1") (pintype "bidirectional"))
      (node (ref "J3") (pin "VBUS2") (pinfunction "VBUS_VBUS2") (pintype "bidirectional"))
      (node (ref "U3") (pin "5") (pinfunction "VCC_5") (pintype "bidirectional"))
    )
    (net (code "85") (name "unconnected-(J1-AUD_BCLK-Pad50)") (class "Default")
      (node (ref "J1") (pin "50") (pinfunction "AUD_BCLK_50") (pintype "bidirectional"))
    )
    (net (code "86") (name "unconnected-(J1-AUD_IN{slash}CAM_PCLK-Pad54)") (class "Default")
      (node (ref "J1") (pin "54") (pinfunction "AUD_IN/CAM_PCLK_54") (pintype "bidirectional"))
    )
    (net (code "87") (name "unconnected-(J1-AUD_LRCLK-Pad52)") (class "Default")
      (node (ref "J1") (pin "52") (pinfunction "AUD_LRCLK_52") (pintype "bidirectional"))
    )
    (net (code "88") (name "unconnected-(J1-AUD_MCLK-Pad58)") (class "Default")
      (node (ref "J1") (pin "58") (pinfunction "AUD_MCLK_58") (pintype "bidirectional"))
    )
    (net (code "89") (name "unconnected-(J1-AUD_OUT{slash}CAM_MCLK-Pad56)") (class "Default")
      (node (ref "J1") (pin "56") (pinfunction "AUD_OUT/CAM_MCLK_56") (pintype "bidirectional"))
    )
    (net (code "90") (name "unconnected-(J1-G8-Pad67)") (class "Default")
      (node (ref "J1") (pin "67") (pinfunction "G8_67") (pintype "bidirectional"))
    )
    (net (code "91") (name "unconnected-(J1-G9{slash}ADC_D-{slash}CAM_HSYNC-Pad65)") (class "Default")
      (node (ref "J1") (pin "65") (pinfunction "G9/ADC_D-/CAM_HSYNC_65") (pintype "bidirectional"))
    )
    (net (code "92") (name "unconnected-(J1-G10{slash}ADC_D+{slash}CAM_VSYNC-Pad63)") (class "Default")
      (node (ref "J1") (pin "63") (pinfunction "G10/ADC_D+/CAM_VSYNC_63") (pintype "bidirectional"))
    )
    (net (code "93") (name "unconnected-(J1-G11-Pad8)") (class "Default")
      (node (ref "J1") (pin "8") (pinfunction "G11_8") (pintype "bidirectional"))
    )
    (net (code "94") (name "unconnected-(J1-RTC_3V-Pad72)") (class "Default")
      (node (ref "J1") (pin "72") (pinfunction "RTC_3V_72") (pintype "bidirectional"))
    )
    (net (code "95") (name "unconnected-(J1-SPI_SDI1{slash}SDIO_DATA0-Pad64)") (class "Default")
      (node (ref "J1") (pin "64") (pinfunction "SPI_SDI1/SDIO_DATA0_64") (pintype "bidirectional"))
    )
    (net (code "96") (name "unconnected-(J5-SWO-Pad6)") (class "Default")
      (node (ref "J5") (pin "6") (pinfunction "SWO_6") (pintype "bidirectional"))
    )
    (net (code "97") (name "unconnected-(J6-EEPROM_WP-Pad40)") (class "Default")
      (node (ref "J6") (pin "40") (pinfunction "EEPROM_WP_40") (pintype "bidirectional"))
    )
    (net (code "98") (name "unconnected-(J6-USB_VIN-Pad70)") (class "Default")
      (node (ref "J6") (pin "70") (pinfunction "USB_VIN_70") (pintype "bidirectional"))
    )
    (net (code "99") (name "unconnected-(J7-CAN-RX-Pad43)") (class "Default")
      (node (ref "J7") (pin "43") (pinfunction "CAN-RX_43") (pintype "bidirectional"))
    )
    (net (code "100") (name "unconnected-(J7-CAN-TX-Pad41)") (class "Default")
      (node (ref "J7") (pin "41") (pinfunction "CAN-TX_41") (pintype "bidirectional"))
    )
    (net (code "101") (name "unconnected-(J7-EEPROM_WP-Pad40)") (class "Default")
      (node (ref "J7") (pin "40") (pinfunction "EEPROM_WP_40") (pintype "bidirectional"))
    )
    (net (code "102") (name "unconnected-(J7-FUNC_CTS-Pad18)") (class "Default")
      (node (ref "J7") (pin "18") (pinfunction "FUNC_CTS_18") (pintype "bidirectional"))
    )
    (net (code "103") (name "unconnected-(J7-FUNC_RTS-Pad16)") (class "Default")
      (node (ref "J7") (pin "16") (pinfunction "FUNC_RTS_16") (pintype "bidirectional"))
    )
    (net (code "104") (name "unconnected-(J7-USBHOST_D+-Pad35)") (class "Default")
      (node (ref "J7") (pin "35") (pinfunction "USBHOST_D+_35") (pintype "bidirectional"))
    )
    (net (code "105") (name "unconnected-(J7-USBHOST_D--Pad37)") (class "Default")
      (node (ref "J7") (pin "37") (pinfunction "USBHOST_D-_37") (pintype "bidirectional"))
    )
    (net (code "106") (name "unconnected-(J7-USB_VIN-Pad70)") (class "Default")
      (node (ref "J7") (pin "70") (pinfunction "USB_VIN_70") (pintype "bidirectional"))
    )
    (net (code "107") (name "unconnected-(J8-PAD1-PadNC1)") (class "Default")
      (node (ref "J8") (pin "NC1") (pinfunction "PAD1_NC1") (pintype "bidirectional"))
    )
    (net (code "108") (name "unconnected-(J8-PAD2-PadNC2)") (class "Default")
      (node (ref "J8") (pin "NC2") (pinfunction "PAD2_NC2") (pintype "bidirectional"))
    )
    (net (code "109") (name "unconnected-(J10-DAT1-Pad8)") (class "Default")
      (node (ref "J10") (pin "8") (pinfunction "DAT1_8") (pintype "bidirectional"))
    )
    (net (code "110") (name "unconnected-(J10-DAT2-Pad1)") (class "Default")
      (node (ref "J10") (pin "1") (pinfunction "DAT2_1") (pintype "bidirectional"))
    )
    (net (code "111") (name "unconnected-(J10-DET-Pad9)") (class "Default")
      (node (ref "J10") (pin "9") (pinfunction "DET_9") (pintype "bidirectional"))
    )
    (net (code "112") (name "unconnected-(U3-IO1-Pad1)") (class "Default")
      (node (ref "U3") (pin "1") (pinfunction "IO1_1") (pintype "bidirectional"))
    )
    (net (code "113") (name "unconnected-(U3-IO2-Pad3)") (class "Default")
      (node (ref "U3") (pin "3") (pinfunction "IO2_3") (pintype "bidirectional"))
    )
  )
)
